# Wio_-_Expansion_Board.net
KiCad netlist of a schematic drawn in EAGLE
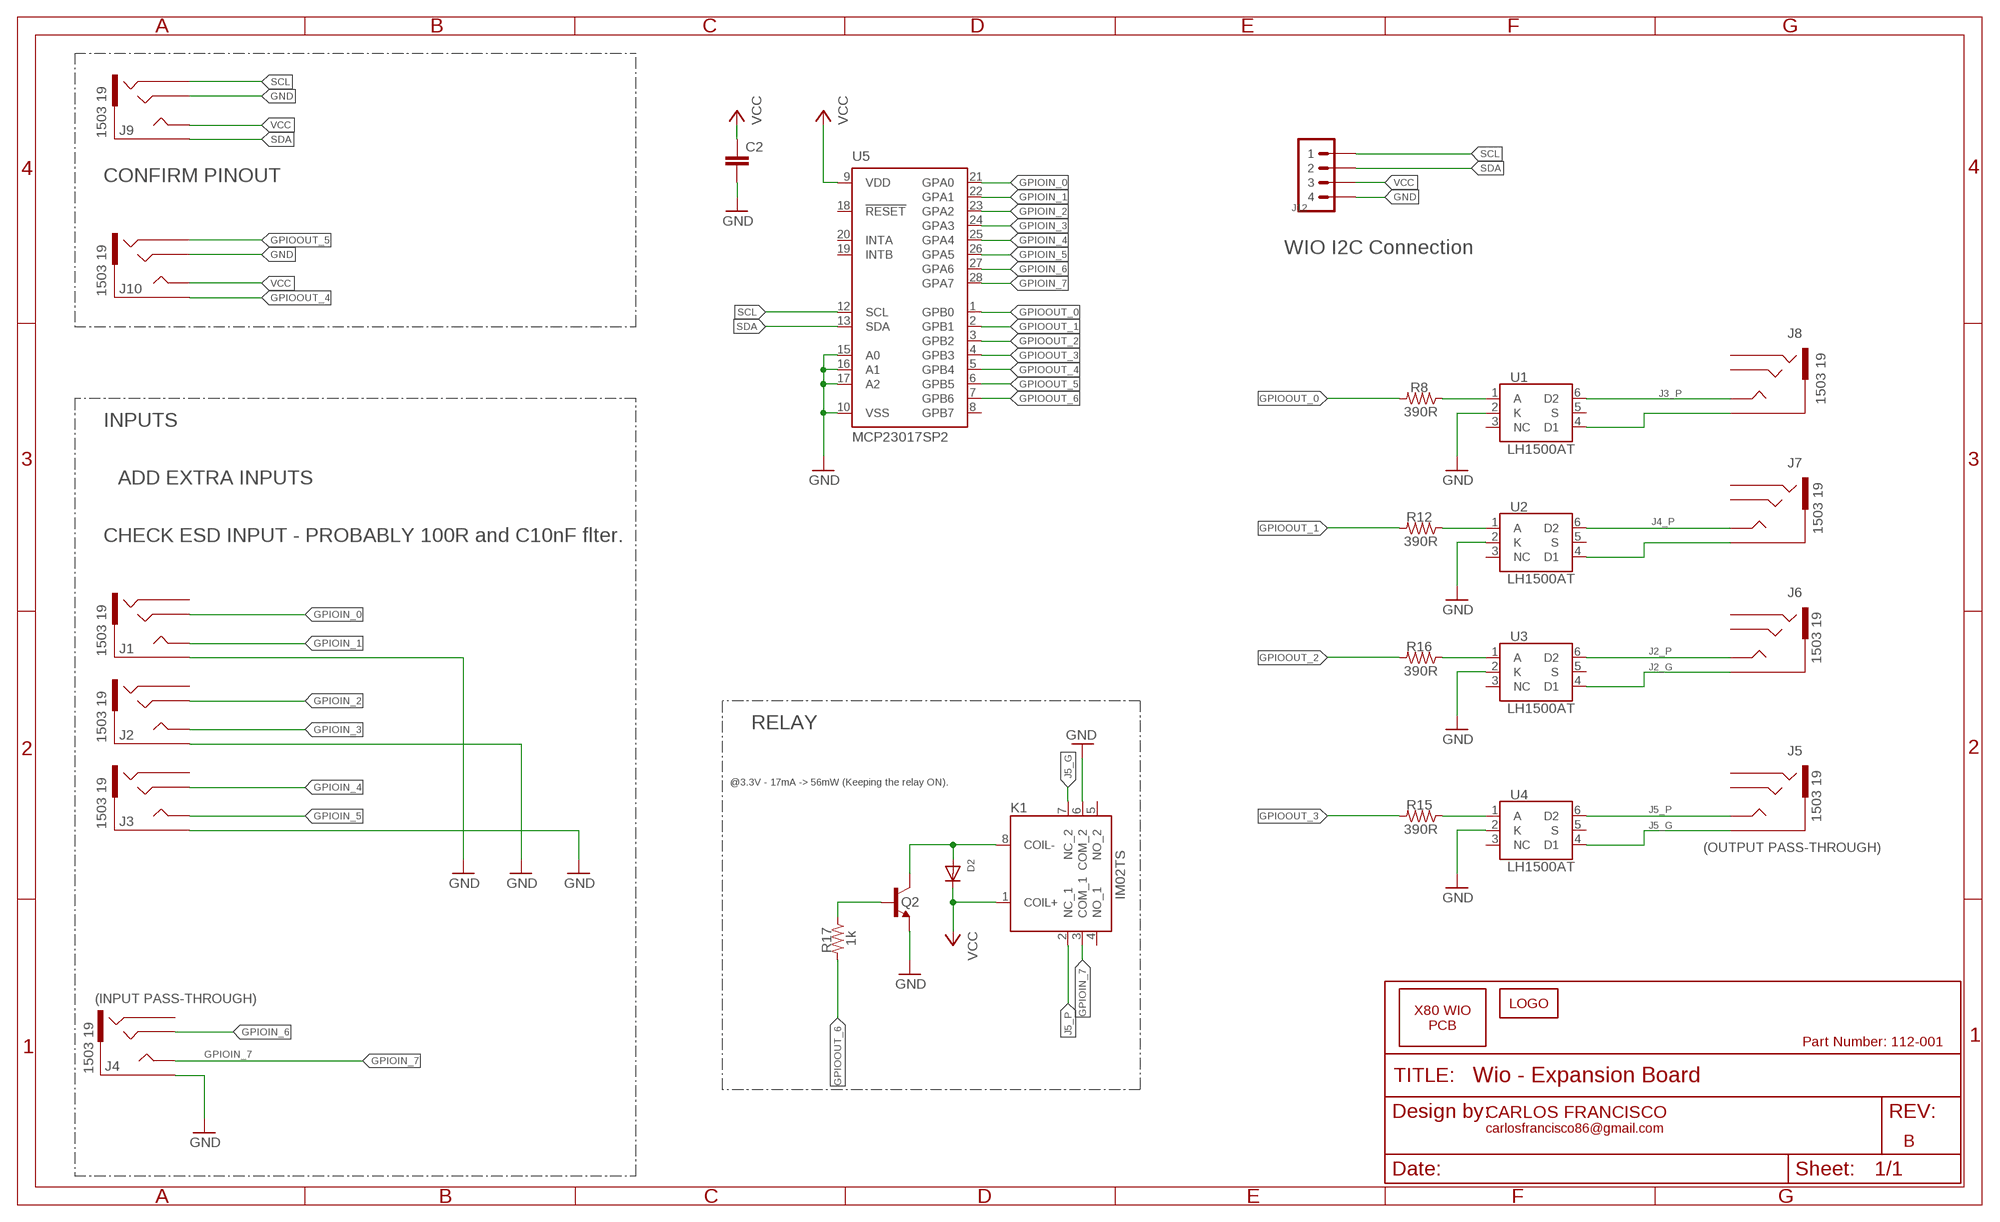
[diagram p0: schematic, sheet 1]

(export (version "E")
  (design (tool "Eeschema 10.0.6"))
  (components
    (comp (ref "C2")
      (value "C-EU025-025X050")
      (footprint "eagle-import:C025-025X050")
      (libsource (lib "eagle-import") (part "C-EU025-025X050"))
    )
    (comp (ref "D2")
      (value "1N4148")
      (footprint "eagle-import:DO-1N4148")
      (fields (field (name "MFR") "ON Semiconductor"))
      (libsource (lib "eagle-import") (part "DIODE-DO-35"))
    )
    (comp (ref "J1")
      (value "1503 19")
      (footprint "eagle-import:1503-19")
      (fields (field (name "MFR") "Lumberg"))
      (libsource (lib "eagle-import") (part "STEREO_JACK-1503-19"))
    )
    (comp (ref "J2")
      (value "1503 19")
      (footprint "eagle-import:1503-19")
      (fields (field (name "MFR") "Lumberg"))
      (libsource (lib "eagle-import") (part "STEREO_JACK-1503-19"))
    )
    (comp (ref "J3")
      (value "1503 19")
      (footprint "eagle-import:1503-19")
      (fields (field (name "MFR") "Lumberg"))
      (libsource (lib "eagle-import") (part "STEREO_JACK-1503-19"))
    )
    (comp (ref "J4")
      (value "1503 19")
      (footprint "eagle-import:1503-19")
      (fields (field (name "MFR") "Lumberg"))
      (libsource (lib "eagle-import") (part "STEREO_JACK-1503-19"))
    )
    (comp (ref "J5")
      (value "1503 19")
      (footprint "eagle-import:1503-19")
      (fields (field (name "MFR") "Lumberg"))
      (libsource (lib "eagle-import") (part "STEREO_JACK-1503-19"))
    )
    (comp (ref "J6")
      (value "1503 19")
      (footprint "eagle-import:1503-19")
      (fields (field (name "MFR") "Lumberg"))
      (libsource (lib "eagle-import") (part "STEREO_JACK-1503-19"))
    )
    (comp (ref "J7")
      (value "1503 19")
      (footprint "eagle-import:1503-19")
      (fields (field (name "MFR") "Lumberg"))
      (libsource (lib "eagle-import") (part "STEREO_JACK-1503-19"))
    )
    (comp (ref "J8")
      (value "1503 19")
      (footprint "eagle-import:1503-19")
      (fields (field (name "MFR") "Lumberg"))
      (libsource (lib "eagle-import") (part "STEREO_JACK-1503-19"))
    )
    (comp (ref "J9")
      (value "1503 19")
      (footprint "eagle-import:1503-19")
      (fields (field (name "MFR") "Lumberg"))
      (libsource (lib "eagle-import") (part "STEREO_JACK-1503-19"))
    )
    (comp (ref "J10")
      (value "1503 19")
      (footprint "eagle-import:1503-19")
      (fields (field (name "MFR") "Lumberg"))
      (libsource (lib "eagle-import") (part "STEREO_JACK-1503-19"))
    )
    (comp (ref "J12")
      (value "4P-2.0-90D")
      (footprint "eagle-import:HW4-2.0-90D")
      (libsource (lib "eagle-import") (part "CONN_04-GROOVE-RA-THT"))
    )
    (comp (ref "K1")
      (value "IM02TS")
      (footprint "eagle-import:IM03TS114620378")
      (fields (field (name "MFR") "TE Connectivity"))
      (libsource (lib "eagle-import") (part "IM02TS"))
    )
    (comp (ref "LOGO1")
      (value "LOGO-10MM")
      (footprint "eagle-import:LOGO_10MM")
      (libsource (lib "eagle-import") (part "LOGO-10MM"))
    )
    (comp (ref "PCB2")
      (value "X80_WIO_PCB-WIO_PCB_V1")
      (footprint "eagle-import:WIO_PCB")
      (libsource (lib "eagle-import") (part "X80_WIO_PCB-WIO_PCB_V1"))
    )
    (comp (ref "Q2")
      (value "PN2222A")
      (footprint "eagle-import:TO92-EBC-OVAL")
      (fields (field (name "MFR") "ON Semiconductor"))
      (libsource (lib "eagle-import") (part "NPN-TO-92"))
    )
    (comp (ref "R8")
      (value "390R")
      (footprint "eagle-import:0204_7")
      (libsource (lib "eagle-import") (part "R-0206-THT-RS"))
    )
    (comp (ref "R12")
      (value "390R")
      (footprint "eagle-import:0204_7")
      (libsource (lib "eagle-import") (part "R-0206-THT-RS"))
    )
    (comp (ref "R15")
      (value "390R")
      (footprint "eagle-import:0204_7")
      (libsource (lib "eagle-import") (part "R-0206-THT-RS"))
    )
    (comp (ref "R16")
      (value "390R")
      (footprint "eagle-import:0204_7")
      (libsource (lib "eagle-import") (part "R-0206-THT-RS"))
    )
    (comp (ref "R17")
      (value "1k")
      (footprint "eagle-import:0204_7")
      (libsource (lib "eagle-import") (part "R-0206-THT-RS"))
    )
    (comp (ref "U1")
      (value "LH1500AT")
      (footprint "eagle-import:DIP762W47P254L880H410Q6N")
      (fields (field (name "MFR") "Vishay"))
      (libsource (lib "eagle-import") (part "SSR-LH1500AT"))
    )
    (comp (ref "U2")
      (value "LH1500AT")
      (footprint "eagle-import:DIP762W47P254L880H410Q6N")
      (fields (field (name "MFR") "Vishay"))
      (libsource (lib "eagle-import") (part "SSR-LH1500AT"))
    )
    (comp (ref "U3")
      (value "LH1500AT")
      (footprint "eagle-import:DIP762W47P254L880H410Q6N")
      (fields (field (name "MFR") "Vishay"))
      (libsource (lib "eagle-import") (part "SSR-LH1500AT"))
    )
    (comp (ref "U4")
      (value "LH1500AT")
      (footprint "eagle-import:DIP762W47P254L880H410Q6N")
      (fields (field (name "MFR") "Vishay"))
      (libsource (lib "eagle-import") (part "SSR-LH1500AT"))
    )
    (comp (ref "U5")
      (value "MCP23017SP2")
      (footprint "eagle-import:DIL28-3-ROUND")
      (libsource (lib "eagle-import") (part "MCP23017SP2"))
    )
  )
  (nets
    (net (code "1") (name "/J2_G") (class "Default")
      (node (ref "J6") (pin "1") (pinfunction "1_1") (pintype "bidirectional"))
      (node (ref "U3") (pin "4") (pinfunction "D1_4") (pintype "bidirectional"))
    )
    (net (code "2") (name "/J2_P") (class "Default")
      (node (ref "J6") (pin "4") (pinfunction "4_4") (pintype "bidirectional"))
      (node (ref "J6") (pin "5") (pinfunction "4_5") (pintype "bidirectional"))
      (node (ref "U3") (pin "6") (pinfunction "D2_6") (pintype "bidirectional"))
    )
    (net (code "3") (name "/J3_P") (class "Default")
      (node (ref "J8") (pin "4") (pinfunction "4_4") (pintype "bidirectional"))
      (node (ref "J8") (pin "5") (pinfunction "4_5") (pintype "bidirectional"))
      (node (ref "U1") (pin "6") (pinfunction "D2_6") (pintype "bidirectional"))
    )
    (net (code "4") (name "/J4_P") (class "Default")
      (node (ref "J7") (pin "4") (pinfunction "4_4") (pintype "bidirectional"))
      (node (ref "J7") (pin "5") (pinfunction "4_5") (pintype "bidirectional"))
      (node (ref "U2") (pin "6") (pinfunction "D2_6") (pintype "bidirectional"))
    )
    (net (code "5") (name "GND") (class "Default")
      (node (ref "C2") (pin "2") (pinfunction "2_2") (pintype "passive"))
      (node (ref "J1") (pin "1") (pinfunction "1_1") (pintype "bidirectional"))
      (node (ref "J10") (pin "3") (pinfunction "3_3") (pintype "bidirectional"))
      (node (ref "J12") (pin "4") (pinfunction "4_4") (pintype "passive"))
      (node (ref "J2") (pin "1") (pinfunction "1_1") (pintype "bidirectional"))
      (node (ref "J3") (pin "1") (pinfunction "1_1") (pintype "bidirectional"))
      (node (ref "J4") (pin "1") (pinfunction "1_1") (pintype "bidirectional"))
      (node (ref "J9") (pin "3") (pinfunction "3_3") (pintype "bidirectional"))
      (node (ref "K1") (pin "6") (pinfunction "COM_2_6") (pintype "bidirectional"))
      (node (ref "Q2") (pin "E") (pinfunction "E_E") (pintype "passive"))
      (node (ref "U1") (pin "2") (pinfunction "K_2") (pintype "bidirectional"))
      (node (ref "U2") (pin "2") (pinfunction "K_2") (pintype "bidirectional"))
      (node (ref "U3") (pin "2") (pinfunction "K_2") (pintype "bidirectional"))
      (node (ref "U4") (pin "2") (pinfunction "K_2") (pintype "bidirectional"))
      (node (ref "U5") (pin "10") (pinfunction "VSS_10") (pintype "power_in"))
      (node (ref "U5") (pin "15") (pinfunction "A0_15") (pintype "input"))
      (node (ref "U5") (pin "16") (pinfunction "A1_16") (pintype "input"))
      (node (ref "U5") (pin "17") (pinfunction "A2_17") (pintype "input"))
    )
    (net (code "6") (name "GPIOIN_0") (class "Default")
      (node (ref "J1") (pin "3") (pinfunction "3_3") (pintype "bidirectional"))
      (node (ref "U5") (pin "21") (pinfunction "GPA0_21") (pintype "bidirectional"))
    )
    (net (code "7") (name "GPIOIN_1") (class "Default")
      (node (ref "J1") (pin "4") (pinfunction "4_4") (pintype "bidirectional"))
      (node (ref "J1") (pin "5") (pinfunction "4_5") (pintype "bidirectional"))
      (node (ref "U5") (pin "22") (pinfunction "GPA1_22") (pintype "bidirectional"))
    )
    (net (code "8") (name "GPIOIN_2") (class "Default")
      (node (ref "J2") (pin "3") (pinfunction "3_3") (pintype "bidirectional"))
      (node (ref "U5") (pin "23") (pinfunction "GPA2_23") (pintype "bidirectional"))
    )
    (net (code "9") (name "GPIOIN_3") (class "Default")
      (node (ref "J2") (pin "4") (pinfunction "4_4") (pintype "bidirectional"))
      (node (ref "J2") (pin "5") (pinfunction "4_5") (pintype "bidirectional"))
      (node (ref "U5") (pin "24") (pinfunction "GPA3_24") (pintype "bidirectional"))
    )
    (net (code "10") (name "GPIOIN_4") (class "Default")
      (node (ref "J3") (pin "3") (pinfunction "3_3") (pintype "bidirectional"))
      (node (ref "U5") (pin "25") (pinfunction "GPA4_25") (pintype "bidirectional"))
    )
    (net (code "11") (name "GPIOIN_5") (class "Default")
      (node (ref "J3") (pin "4") (pinfunction "4_4") (pintype "bidirectional"))
      (node (ref "J3") (pin "5") (pinfunction "4_5") (pintype "bidirectional"))
      (node (ref "U5") (pin "26") (pinfunction "GPA5_26") (pintype "bidirectional"))
    )
    (net (code "12") (name "GPIOIN_6") (class "Default")
      (node (ref "J4") (pin "3") (pinfunction "3_3") (pintype "bidirectional"))
      (node (ref "U5") (pin "27") (pinfunction "GPA6_27") (pintype "bidirectional"))
    )
    (net (code "13") (name "GPIOIN_7") (class "Default")
      (node (ref "J4") (pin "4") (pinfunction "4_4") (pintype "bidirectional"))
      (node (ref "J4") (pin "5") (pinfunction "4_5") (pintype "bidirectional"))
      (node (ref "K1") (pin "3") (pinfunction "COM_1_3") (pintype "bidirectional"))
      (node (ref "U5") (pin "28") (pinfunction "GPA7_28") (pintype "bidirectional"))
    )
    (net (code "14") (name "GPIOOUT_0") (class "Default")
      (node (ref "R8") (pin "1") (pinfunction "1_1") (pintype "passive"))
      (node (ref "U5") (pin "1") (pinfunction "GPB0_1") (pintype "bidirectional"))
    )
    (net (code "15") (name "GPIOOUT_1") (class "Default")
      (node (ref "R12") (pin "1") (pinfunction "1_1") (pintype "passive"))
      (node (ref "U5") (pin "2") (pinfunction "GPB1_2") (pintype "bidirectional"))
    )
    (net (code "16") (name "GPIOOUT_2") (class "Default")
      (node (ref "R16") (pin "1") (pinfunction "1_1") (pintype "passive"))
      (node (ref "U5") (pin "3") (pinfunction "GPB2_3") (pintype "bidirectional"))
    )
    (net (code "17") (name "GPIOOUT_3") (class "Default")
      (node (ref "R15") (pin "1") (pinfunction "1_1") (pintype "passive"))
      (node (ref "U5") (pin "4") (pinfunction "GPB3_4") (pintype "bidirectional"))
    )
    (net (code "18") (name "GPIOOUT_4") (class "Default")
      (node (ref "J10") (pin "1") (pinfunction "1_1") (pintype "bidirectional"))
      (node (ref "U5") (pin "5") (pinfunction "GPB4_5") (pintype "bidirectional"))
    )
    (net (code "19") (name "GPIOOUT_5") (class "Default")
      (node (ref "J10") (pin "2") (pinfunction "2_2") (pintype "bidirectional"))
      (node (ref "U5") (pin "6") (pinfunction "GPB5_6") (pintype "bidirectional"))
    )
    (net (code "20") (name "GPIOOUT_6") (class "Default")
      (node (ref "R17") (pin "1") (pinfunction "1_1") (pintype "passive"))
      (node (ref "U5") (pin "7") (pinfunction "GPB6_7") (pintype "bidirectional"))
    )
    (net (code "21") (name "J5_G") (class "Default")
      (node (ref "J5") (pin "1") (pinfunction "1_1") (pintype "bidirectional"))
      (node (ref "K1") (pin "7") (pinfunction "NC_2_7") (pintype "bidirectional"))
      (node (ref "U4") (pin "4") (pinfunction "D1_4") (pintype "bidirectional"))
    )
    (net (code "22") (name "J5_P") (class "Default")
      (node (ref "J5") (pin "4") (pinfunction "4_4") (pintype "bidirectional"))
      (node (ref "J5") (pin "5") (pinfunction "4_5") (pintype "bidirectional"))
      (node (ref "K1") (pin "2") (pinfunction "NC_1_2") (pintype "bidirectional"))
      (node (ref "U4") (pin "6") (pinfunction "D2_6") (pintype "bidirectional"))
    )
    (net (code "23") (name "Net-(K1-COIL-)") (class "Default")
      (node (ref "D2") (pin "A") (pinfunction "A_A") (pintype "passive"))
      (node (ref "K1") (pin "8") (pinfunction "COIL-_8") (pintype "bidirectional"))
      (node (ref "Q2") (pin "C") (pinfunction "C_C") (pintype "passive"))
    )
    (net (code "24") (name "Net-(Q2-PadB)") (class "Default")
      (node (ref "Q2") (pin "B") (pinfunction "B_B") (pintype "passive"))
      (node (ref "R17") (pin "2") (pinfunction "2_2") (pintype "passive"))
    )
    (net (code "25") (name "Net-(U1-A)") (class "Default")
      (node (ref "R8") (pin "2") (pinfunction "2_2") (pintype "passive"))
      (node (ref "U1") (pin "1") (pinfunction "A_1") (pintype "bidirectional"))
    )
    (net (code "26") (name "Net-(U1-D1)") (class "Default")
      (node (ref "J8") (pin "1") (pinfunction "1_1") (pintype "bidirectional"))
      (node (ref "U1") (pin "4") (pinfunction "D1_4") (pintype "bidirectional"))
    )
    (net (code "27") (name "Net-(U2-A)") (class "Default")
      (node (ref "R12") (pin "2") (pinfunction "2_2") (pintype "passive"))
      (node (ref "U2") (pin "1") (pinfunction "A_1") (pintype "bidirectional"))
    )
    (net (code "28") (name "Net-(U2-D1)") (class "Default")
      (node (ref "J7") (pin "1") (pinfunction "1_1") (pintype "bidirectional"))
      (node (ref "U2") (pin "4") (pinfunction "D1_4") (pintype "bidirectional"))
    )
    (net (code "29") (name "Net-(U3-A)") (class "Default")
      (node (ref "R16") (pin "2") (pinfunction "2_2") (pintype "passive"))
      (node (ref "U3") (pin "1") (pinfunction "A_1") (pintype "bidirectional"))
    )
    (net (code "30") (name "Net-(U4-A)") (class "Default")
      (node (ref "R15") (pin "2") (pinfunction "2_2") (pintype "passive"))
      (node (ref "U4") (pin "1") (pinfunction "A_1") (pintype "bidirectional"))
    )
    (net (code "31") (name "SCL") (class "Default")
      (node (ref "J12") (pin "1") (pinfunction "1_1") (pintype "passive"))
      (node (ref "J9") (pin "2") (pinfunction "2_2") (pintype "bidirectional"))
      (node (ref "U5") (pin "12") (pinfunction "SCL_12") (pintype "input"))
    )
    (net (code "32") (name "SDA") (class "Default")
      (node (ref "J12") (pin "2") (pinfunction "2_2") (pintype "passive"))
      (node (ref "J9") (pin "1") (pinfunction "1_1") (pintype "bidirectional"))
      (node (ref "U5") (pin "13") (pinfunction "SDA_13") (pintype "bidirectional"))
    )
    (net (code "33") (name "VCC") (class "Default")
      (node (ref "C2") (pin "1") (pinfunction "1_1") (pintype "passive"))
      (node (ref "D2") (pin "C") (pinfunction "C_C") (pintype "passive"))
      (node (ref "J10") (pin "4") (pinfunction "4_4") (pintype "bidirectional"))
      (node (ref "J10") (pin "5") (pinfunction "4_5") (pintype "bidirectional"))
      (node (ref "J12") (pin "3") (pinfunction "3_3") (pintype "passive"))
      (node (ref "J9") (pin "4") (pinfunction "4_4") (pintype "bidirectional"))
      (node (ref "J9") (pin "5") (pinfunction "4_5") (pintype "bidirectional"))
      (node (ref "K1") (pin "1") (pinfunction "COIL+_1") (pintype "bidirectional"))
      (node (ref "U5") (pin "9") (pinfunction "VDD_9") (pintype "power_in"))
    )
    (net (code "34") (name "unconnected-(J1-Pad2)") (class "Default")
      (node (ref "J1") (pin "2") (pinfunction "2_2") (pintype "bidirectional"))
    )
    (net (code "35") (name "unconnected-(J2-Pad2)") (class "Default")
      (node (ref "J2") (pin "2") (pinfunction "2_2") (pintype "bidirectional"))
    )
    (net (code "36") (name "unconnected-(J3-Pad2)") (class "Default")
      (node (ref "J3") (pin "2") (pinfunction "2_2") (pintype "bidirectional"))
    )
    (net (code "37") (name "unconnected-(J4-Pad2)") (class "Default")
      (node (ref "J4") (pin "2") (pinfunction "2_2") (pintype "bidirectional"))
    )
    (net (code "38") (name "unconnected-(J5-Pad2)") (class "Default")
      (node (ref "J5") (pin "2") (pinfunction "2_2") (pintype "bidirectional"))
    )
    (net (code "39") (name "unconnected-(J5-Pad3)") (class "Default")
      (node (ref "J5") (pin "3") (pinfunction "3_3") (pintype "bidirectional"))
    )
    (net (code "40") (name "unconnected-(J6-Pad2)") (class "Default")
      (node (ref "J6") (pin "2") (pinfunction "2_2") (pintype "bidirectional"))
    )
    (net (code "41") (name "unconnected-(J6-Pad3)") (class "Default")
      (node (ref "J6") (pin "3") (pinfunction "3_3") (pintype "bidirectional"))
    )
    (net (code "42") (name "unconnected-(J7-Pad2)") (class "Default")
      (node (ref "J7") (pin "2") (pinfunction "2_2") (pintype "bidirectional"))
    )
    (net (code "43") (name "unconnected-(J7-Pad3)") (class "Default")
      (node (ref "J7") (pin "3") (pinfunction "3_3") (pintype "bidirectional"))
    )
    (net (code "44") (name "unconnected-(J8-Pad2)") (class "Default")
      (node (ref "J8") (pin "2") (pinfunction "2_2") (pintype "bidirectional"))
    )
    (net (code "45") (name "unconnected-(J8-Pad3)") (class "Default")
      (node (ref "J8") (pin "3") (pinfunction "3_3") (pintype "bidirectional"))
    )
    (net (code "46") (name "unconnected-(K1-NO_1-Pad4)") (class "Default")
      (node (ref "K1") (pin "4") (pinfunction "NO_1_4") (pintype "bidirectional"))
    )
    (net (code "47") (name "unconnected-(K1-NO_2-Pad5)") (class "Default")
      (node (ref "K1") (pin "5") (pinfunction "NO_2_5") (pintype "bidirectional"))
    )
    (net (code "48") (name "unconnected-(U1-NC-Pad3)") (class "Default")
      (node (ref "U1") (pin "3") (pinfunction "NC_3") (pintype "no_connect"))
    )
    (net (code "49") (name "unconnected-(U1-S-Pad5)") (class "Default")
      (node (ref "U1") (pin "5") (pinfunction "S_5") (pintype "bidirectional"))
    )
    (net (code "50") (name "unconnected-(U2-NC-Pad3)") (class "Default")
      (node (ref "U2") (pin "3") (pinfunction "NC_3") (pintype "no_connect"))
    )
    (net (code "51") (name "unconnected-(U2-S-Pad5)") (class "Default")
      (node (ref "U2") (pin "5") (pinfunction "S_5") (pintype "bidirectional"))
    )
    (net (code "52") (name "unconnected-(U3-NC-Pad3)") (class "Default")
      (node (ref "U3") (pin "3") (pinfunction "NC_3") (pintype "no_connect"))
    )
    (net (code "53") (name "unconnected-(U3-S-Pad5)") (class "Default")
      (node (ref "U3") (pin "5") (pinfunction "S_5") (pintype "bidirectional"))
    )
    (net (code "54") (name "unconnected-(U4-NC-Pad3)") (class "Default")
      (node (ref "U4") (pin "3") (pinfunction "NC_3") (pintype "no_connect"))
    )
    (net (code "55") (name "unconnected-(U4-S-Pad5)") (class "Default")
      (node (ref "U4") (pin "5") (pinfunction "S_5") (pintype "bidirectional"))
    )
    (net (code "56") (name "unconnected-(U5-GPB7-Pad8)") (class "Default")
      (node (ref "U5") (pin "8") (pinfunction "GPB7_8") (pintype "bidirectional"))
    )
    (net (code "57") (name "unconnected-(U5-INTA-Pad20)") (class "Default")
      (node (ref "U5") (pin "20") (pinfunction "INTA_20") (pintype "output"))
    )
    (net (code "58") (name "unconnected-(U5-INTB-Pad19)") (class "Default")
      (node (ref "U5") (pin "19") (pinfunction "INTB_19") (pintype "output"))
    )
    (net (code "59") (name "unconnected-(U5-~{RESET}-Pad18)") (class "Default")
      (node (ref "U5") (pin "18") (pinfunction "~{RESET}_18") (pintype "input"))
    )
  )
)
